# BMW_final.net
KiCad netlist of a schematic drawn in EAGLE
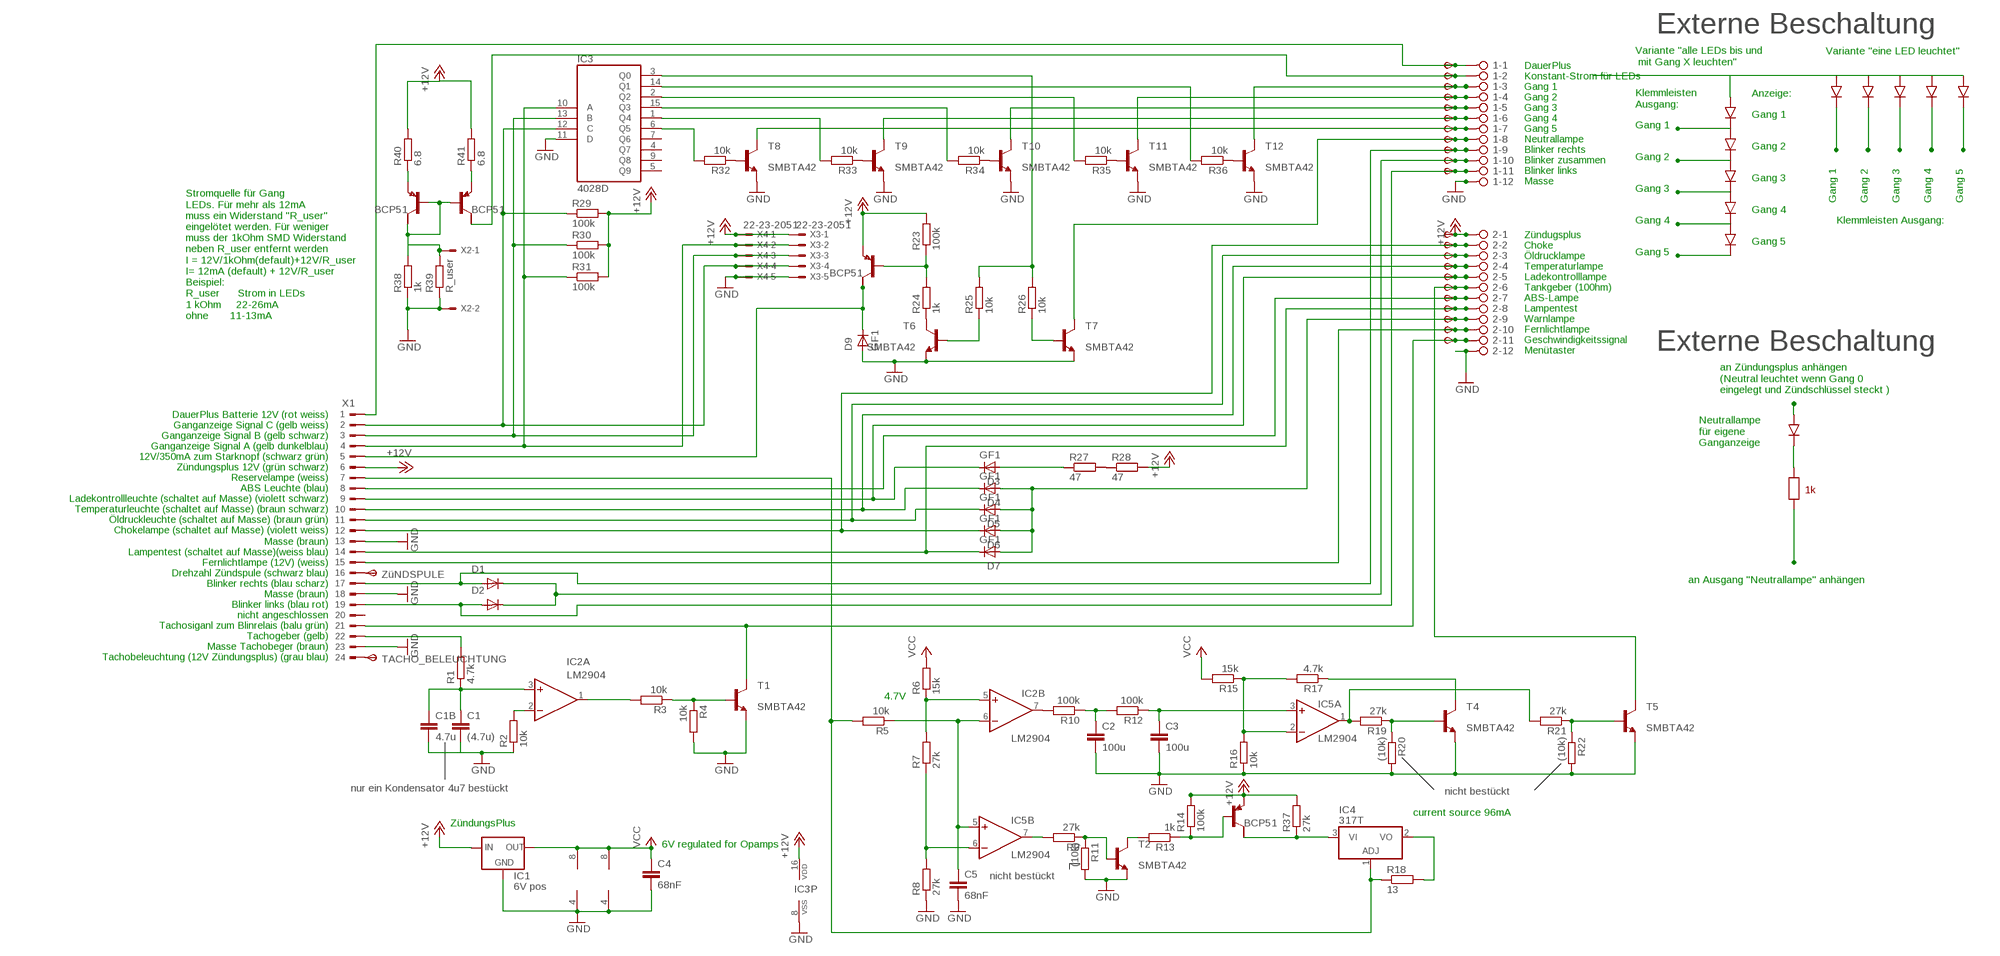
[diagram p0: schematic, sheet 1]

(export (version "E")
  (design (tool "Eeschema 10.0.6"))
  (components
    (comp (ref "1")
      (value "2081-1132")
      (footprint "eagle-import:12-PIN")
      (libsource (lib "eagle-import") (part "2081-1132"))
    )
    (comp (ref "2")
      (value "2081-1132")
      (footprint "eagle-import:12-PIN")
      (libsource (lib "eagle-import") (part "2081-1132"))
    )
    (comp (ref "C1")
      (value "(4.7u)")
      (footprint "eagle-import:C1206")
      (libsource (lib "eagle-import") (part "C-EUC1206"))
    )
    (comp (ref "C1B")
      (value "4.7u")
      (footprint "eagle-import:C0805K")
      (libsource (lib "eagle-import") (part "C-EUC0805K"))
    )
    (comp (ref "C2")
      (value "100u")
      (footprint "eagle-import:C1206K")
      (libsource (lib "eagle-import") (part "C-EUC1206K"))
    )
    (comp (ref "C3")
      (value "100u")
      (footprint "eagle-import:C1206K")
      (libsource (lib "eagle-import") (part "C-EUC1206K"))
    )
    (comp (ref "C4")
      (value "68nF")
      (footprint "eagle-import:C1206K")
      (libsource (lib "eagle-import") (part "C-EUC1206K"))
    )
    (comp (ref "C5")
      (value "68nF")
      (footprint "eagle-import:C1206K")
      (libsource (lib "eagle-import") (part "C-EUC1206K"))
    )
    (comp (ref "D1")
      (value "GF1")
      (footprint "eagle-import:SMA-DO214AC")
      (libsource (lib "eagle-import") (part "GF1"))
    )
    (comp (ref "D2")
      (value "GF1")
      (footprint "eagle-import:SMA-DO214AC")
      (libsource (lib "eagle-import") (part "GF1"))
    )
    (comp (ref "D3")
      (value "GF1")
      (footprint "eagle-import:SMA-DO214AC")
      (libsource (lib "eagle-import") (part "GF1"))
    )
    (comp (ref "D4")
      (value "GF1")
      (footprint "eagle-import:SMA-DO214AC")
      (libsource (lib "eagle-import") (part "GF1"))
    )
    (comp (ref "D5")
      (value "GF1")
      (footprint "eagle-import:SMA-DO214AC")
      (libsource (lib "eagle-import") (part "GF1"))
    )
    (comp (ref "D6")
      (value "GF1")
      (footprint "eagle-import:SMA-DO214AC")
      (libsource (lib "eagle-import") (part "GF1"))
    )
    (comp (ref "D7")
      (value "GF1")
      (footprint "eagle-import:SMA-DO214AC")
      (libsource (lib "eagle-import") (part "GF1"))
    )
    (comp (ref "D9")
      (value "GF1")
      (footprint "eagle-import:SMA-DO214AC")
      (libsource (lib "eagle-import") (part "GF1"))
    )
    (comp (ref "IC1")
      (value "6V pos")
      (footprint "eagle-import:78LXX")
      (libsource (lib "eagle-import") (part "78LXX"))
    )
    (comp (ref "IC2")
      (value "LM2904")
      (footprint "eagle-import:SO08")
      (fields (field (name "IC") "LM2904"))
      (libsource (lib "eagle-import") (part "LM358D"))
    )
    (comp (ref "IC3")
      (value "4028D")
      (footprint "eagle-import:SO16")
      (libsource (lib "eagle-import") (part "4028D"))
    )
    (comp (ref "IC4")
      (value "317T")
      (footprint "eagle-import:TO220H")
      (libsource (lib "eagle-import") (part "317T"))
    )
    (comp (ref "IC5")
      (value "LM2904")
      (footprint "eagle-import:SO08")
      (libsource (lib "eagle-import") (part "linear_BMW_LM358D"))
    )
    (comp (ref "R1")
      (value "4.7k")
      (footprint "eagle-import:R0805")
      (libsource (lib "eagle-import") (part "R-EU_R0805"))
    )
    (comp (ref "R2")
      (value "10k")
      (footprint "eagle-import:R0805")
      (libsource (lib "eagle-import") (part "R-EU_R0805"))
    )
    (comp (ref "R3")
      (value "10k")
      (footprint "eagle-import:R0805")
      (libsource (lib "eagle-import") (part "R-EU_R0805"))
    )
    (comp (ref "R4")
      (value "10k")
      (footprint "eagle-import:R0805")
      (libsource (lib "eagle-import") (part "R-EU_R0805"))
    )
    (comp (ref "R5")
      (value "10k")
      (footprint "eagle-import:R0805")
      (libsource (lib "eagle-import") (part "R-EU_R0805"))
    )
    (comp (ref "R6")
      (value "15k")
      (footprint "eagle-import:R0805")
      (libsource (lib "eagle-import") (part "R-EU_R0805"))
    )
    (comp (ref "R7")
      (value "27k")
      (footprint "eagle-import:R0805")
      (libsource (lib "eagle-import") (part "R-EU_R0805"))
    )
    (comp (ref "R8")
      (value "27k")
      (footprint "eagle-import:R0805")
      (libsource (lib "eagle-import") (part "R-EU_R0805"))
    )
    (comp (ref "R9")
      (value "27k")
      (footprint "eagle-import:R0805")
      (libsource (lib "eagle-import") (part "R-EU_R0805"))
    )
    (comp (ref "R10")
      (value "100k")
      (footprint "eagle-import:R0805")
      (libsource (lib "eagle-import") (part "R-EU_R0805"))
    )
    (comp (ref "R11")
      (value "(10k)")
      (footprint "eagle-import:R0805")
      (libsource (lib "eagle-import") (part "R-EU_R0805"))
    )
    (comp (ref "R12")
      (value "100k")
      (footprint "eagle-import:R0805")
      (libsource (lib "eagle-import") (part "R-EU_R0805"))
    )
    (comp (ref "R13")
      (value "1k")
      (footprint "eagle-import:R0805")
      (libsource (lib "eagle-import") (part "R-EU_R0805"))
    )
    (comp (ref "R14")
      (value "100k")
      (footprint "eagle-import:R0805")
      (libsource (lib "eagle-import") (part "R-EU_R0805"))
    )
    (comp (ref "R15")
      (value "15k")
      (footprint "eagle-import:R0805")
      (libsource (lib "eagle-import") (part "R-EU_R0805"))
    )
    (comp (ref "R16")
      (value "10k")
      (footprint "eagle-import:R0805")
      (libsource (lib "eagle-import") (part "R-EU_R0805"))
    )
    (comp (ref "R17")
      (value "4.7k")
      (footprint "eagle-import:R0805")
      (libsource (lib "eagle-import") (part "R-EU_R0805"))
    )
    (comp (ref "R18")
      (value "13")
      (footprint "eagle-import:0207_10")
      (libsource (lib "eagle-import") (part "R-EU_0207/10"))
    )
    (comp (ref "R19")
      (value "27k")
      (footprint "eagle-import:R0805")
      (libsource (lib "eagle-import") (part "R-EU_R0805"))
    )
    (comp (ref "R20")
      (value "(10k)")
      (footprint "eagle-import:R0805")
      (libsource (lib "eagle-import") (part "R-EU_R0805"))
    )
    (comp (ref "R21")
      (value "27k")
      (footprint "eagle-import:R0805")
      (libsource (lib "eagle-import") (part "R-EU_R0805"))
    )
    (comp (ref "R22")
      (value "(10k)")
      (footprint "eagle-import:R0805")
      (libsource (lib "eagle-import") (part "R-EU_R0805"))
    )
    (comp (ref "R23")
      (value "100k")
      (footprint "eagle-import:R0805")
      (libsource (lib "eagle-import") (part "R-EU_R0805"))
    )
    (comp (ref "R24")
      (value "1k")
      (footprint "eagle-import:R0805")
      (libsource (lib "eagle-import") (part "R-EU_R0805"))
    )
    (comp (ref "R25")
      (value "10k")
      (footprint "eagle-import:R0805")
      (libsource (lib "eagle-import") (part "R-EU_R0805"))
    )
    (comp (ref "R26")
      (value "10k")
      (footprint "eagle-import:R0805")
      (libsource (lib "eagle-import") (part "R-EU_R0805"))
    )
    (comp (ref "R27")
      (value "47")
      (footprint "eagle-import:V235_17")
      (libsource (lib "eagle-import") (part "R-EU_V235/17"))
    )
    (comp (ref "R28")
      (value "47")
      (footprint "eagle-import:V235_17")
      (libsource (lib "eagle-import") (part "R-EU_V235/17"))
    )
    (comp (ref "R29")
      (value "100k")
      (footprint "eagle-import:R0805")
      (libsource (lib "eagle-import") (part "R-EU_R0805"))
    )
    (comp (ref "R30")
      (value "100k")
      (footprint "eagle-import:R0805")
      (libsource (lib "eagle-import") (part "R-EU_R0805"))
    )
    (comp (ref "R31")
      (value "100k")
      (footprint "eagle-import:R0805")
      (libsource (lib "eagle-import") (part "R-EU_R0805"))
    )
    (comp (ref "R32")
      (value "10k")
      (footprint "eagle-import:R0805")
      (libsource (lib "eagle-import") (part "R-EU_R0805"))
    )
    (comp (ref "R33")
      (value "10k")
      (footprint "eagle-import:R0805")
      (libsource (lib "eagle-import") (part "R-EU_R0805"))
    )
    (comp (ref "R34")
      (value "10k")
      (footprint "eagle-import:R0805")
      (libsource (lib "eagle-import") (part "R-EU_R0805"))
    )
    (comp (ref "R35")
      (value "10k")
      (footprint "eagle-import:R0805")
      (libsource (lib "eagle-import") (part "R-EU_R0805"))
    )
    (comp (ref "R36")
      (value "10k")
      (footprint "eagle-import:R0805")
      (libsource (lib "eagle-import") (part "R-EU_R0805"))
    )
    (comp (ref "R37")
      (value "27k")
      (footprint "eagle-import:R0805")
      (libsource (lib "eagle-import") (part "R-EU_R0805"))
    )
    (comp (ref "R38")
      (value "1k")
      (footprint "eagle-import:R0805")
      (libsource (lib "eagle-import") (part "R-EU_R0805"))
    )
    (comp (ref "R39")
      (value "R_user")
      (footprint "eagle-import:R0805")
      (libsource (lib "eagle-import") (part "R-EU_R0805"))
    )
    (comp (ref "R40")
      (value "6.8")
      (footprint "eagle-import:R0805")
      (libsource (lib "eagle-import") (part "R-EU_R0805"))
    )
    (comp (ref "R41")
      (value "6.8")
      (footprint "eagle-import:R0805")
      (libsource (lib "eagle-import") (part "R-EU_R0805"))
    )
    (comp (ref "T")
      (value "BCP53T1")
      (footprint "eagle-import:SOT223")
      (fields (field (name "T") "BCP51"))
      (libsource (lib "eagle-import") (part "BCP53T1"))
    )
    (comp (ref "T1")
      (value "MMBTA42LT1-NPN-SOT23-BEC")
      (footprint "eagle-import:SOT23-BEC")
      (fields (field (name "T") "SMBTA42"))
      (libsource (lib "eagle-import") (part "-NPN-SOT23-BECMMBTA42LT1"))
    )
    (comp (ref "T2")
      (value "MMBTA42LT1-NPN-SOT23-BEC")
      (footprint "eagle-import:SOT23-BEC")
      (fields (field (name "T") "SMBTA42"))
      (libsource (lib "eagle-import") (part "-NPN-SOT23-BECMMBTA42LT1"))
    )
    (comp (ref "T3")
      (value "BCP53T1")
      (footprint "eagle-import:SOT223")
      (fields (field (name "T") "BCP51"))
      (libsource (lib "eagle-import") (part "BCP53T1"))
    )
    (comp (ref "T4")
      (value "MMBTA42LT1-NPN-SOT23-BEC")
      (footprint "eagle-import:SOT23-BEC")
      (fields (field (name "T") "SMBTA42"))
      (libsource (lib "eagle-import") (part "-NPN-SOT23-BECMMBTA42LT1"))
    )
    (comp (ref "T5")
      (value "MMBTA42LT1-NPN-SOT23-BEC")
      (footprint "eagle-import:SOT23-BEC")
      (fields (field (name "T") "SMBTA42"))
      (libsource (lib "eagle-import") (part "-NPN-SOT23-BECMMBTA42LT1"))
    )
    (comp (ref "T6")
      (value "MMBTA42LT1-NPN-SOT23-BEC")
      (footprint "eagle-import:SOT23-BEC")
      (fields (field (name "T") "SMBTA42"))
      (libsource (lib "eagle-import") (part "-NPN-SOT23-BECMMBTA42LT1"))
    )
    (comp (ref "T7")
      (value "MMBTA42LT1-NPN-SOT23-BEC")
      (footprint "eagle-import:SOT23-BEC")
      (fields (field (name "T") "SMBTA42"))
      (libsource (lib "eagle-import") (part "-NPN-SOT23-BECMMBTA42LT1"))
    )
    (comp (ref "T8")
      (value "MMBTA42LT1-NPN-SOT23-BEC")
      (footprint "eagle-import:SOT23-BEC")
      (fields (field (name "T") "SMBTA42"))
      (libsource (lib "eagle-import") (part "-NPN-SOT23-BECMMBTA42LT1"))
    )
    (comp (ref "T9")
      (value "MMBTA42LT1-NPN-SOT23-BEC")
      (footprint "eagle-import:SOT23-BEC")
      (fields (field (name "T") "SMBTA42"))
      (libsource (lib "eagle-import") (part "-NPN-SOT23-BECMMBTA42LT1"))
    )
    (comp (ref "T10")
      (value "MMBTA42LT1-NPN-SOT23-BEC")
      (footprint "eagle-import:SOT23-BEC")
      (fields (field (name "T") "SMBTA42"))
      (libsource (lib "eagle-import") (part "-NPN-SOT23-BECMMBTA42LT1"))
    )
    (comp (ref "T11")
      (value "MMBTA42LT1-NPN-SOT23-BEC")
      (footprint "eagle-import:SOT23-BEC")
      (fields (field (name "T") "SMBTA42"))
      (libsource (lib "eagle-import") (part "-NPN-SOT23-BECMMBTA42LT1"))
    )
    (comp (ref "T12")
      (value "MMBTA42LT1-NPN-SOT23-BEC")
      (footprint "eagle-import:SOT23-BEC")
      (fields (field (name "T") "SMBTA42"))
      (libsource (lib "eagle-import") (part "-NPN-SOT23-BECMMBTA42LT1"))
    )
    (comp (ref "T13")
      (value "BCP53T1")
      (footprint "eagle-import:SOT223")
      (fields (field (name "T") "BCP51"))
      (libsource (lib "eagle-import") (part "BCP53T1"))
    )
    (comp (ref "T14")
      (value "BCP53T1")
      (footprint "eagle-import:SOT223")
      (fields (field (name "T") "BCP51"))
      (libsource (lib "eagle-import") (part "BCP53T1"))
    )
    (comp (ref "TACHO_BELEUCHTUNG")
      (value "TPSP1_1MM")
      (footprint "eagle-import:P1_1.0MM")
      (libsource (lib "eagle-import") (part "TPSP1_1MM"))
    )
    (comp (ref "TP1")
      (value "TPSB1,27")
      (footprint "eagle-import:B1,27")
      (libsource (lib "eagle-import") (part "TPSB1,27"))
    )
    (comp (ref "TP2")
      (value "TPSB1,27")
      (footprint "eagle-import:B1,27")
      (libsource (lib "eagle-import") (part "TPSB1,27"))
    )
    (comp (ref "TP3")
      (value "TPSB1,27")
      (footprint "eagle-import:B1,27")
      (libsource (lib "eagle-import") (part "TPSB1,27"))
    )
    (comp (ref "TP4")
      (value "TPSB1,27")
      (footprint "eagle-import:B1,27")
      (libsource (lib "eagle-import") (part "TPSB1,27"))
    )
    (comp (ref "TP5")
      (value "TPSB1,27")
      (footprint "eagle-import:B1,27")
      (libsource (lib "eagle-import") (part "TPSB1,27"))
    )
    (comp (ref "TP6")
      (value "TPSB1,27")
      (footprint "eagle-import:B1,27")
      (libsource (lib "eagle-import") (part "TPSB1,27"))
    )
    (comp (ref "TP7")
      (value "TPSB1,27")
      (footprint "eagle-import:B1,27")
      (libsource (lib "eagle-import") (part "TPSB1,27"))
    )
    (comp (ref "TP8")
      (value "TPSB1,27")
      (footprint "eagle-import:B1,27")
      (libsource (lib "eagle-import") (part "TPSB1,27"))
    )
    (comp (ref "TP9")
      (value "TPSB1,27")
      (footprint "eagle-import:B1,27")
      (libsource (lib "eagle-import") (part "TPSB1,27"))
    )
    (comp (ref "TP10")
      (value "TPSB1,27")
      (footprint "eagle-import:B1,27")
      (libsource (lib "eagle-import") (part "TPSB1,27"))
    )
    (comp (ref "TP11")
      (value "TPSB1,27")
      (footprint "eagle-import:B1,27")
      (libsource (lib "eagle-import") (part "TPSB1,27"))
    )
    (comp (ref "TP12")
      (value "TPSB1,27")
      (footprint "eagle-import:B1,27")
      (libsource (lib "eagle-import") (part "TPSB1,27"))
    )
    (comp (ref "TP16")
      (value "TPSB1,27")
      (footprint "eagle-import:B1,27")
      (libsource (lib "eagle-import") (part "TPSB1,27"))
    )
    (comp (ref "TP17")
      (value "TPSB1,27")
      (footprint "eagle-import:B1,27")
      (libsource (lib "eagle-import") (part "TPSB1,27"))
    )
    (comp (ref "TP18")
      (value "TPSB1,27")
      (footprint "eagle-import:B1,27")
      (libsource (lib "eagle-import") (part "TPSB1,27"))
    )
    (comp (ref "TP19")
      (value "TPSB1,27")
      (footprint "eagle-import:B1,27")
      (libsource (lib "eagle-import") (part "TPSB1,27"))
    )
    (comp (ref "TP21")
      (value "TPSB1,27")
      (footprint "eagle-import:B1,27")
      (libsource (lib "eagle-import") (part "TPSB1,27"))
    )
    (comp (ref "TP22")
      (value "TPSB1,27")
      (footprint "eagle-import:B1,27")
      (libsource (lib "eagle-import") (part "TPSB1,27"))
    )
    (comp (ref "TP23")
      (value "TPSB1,27")
      (footprint "eagle-import:B1,27")
      (libsource (lib "eagle-import") (part "TPSB1,27"))
    )
    (comp (ref "TP24")
      (value "TPSB1,27")
      (footprint "eagle-import:B1,27")
      (libsource (lib "eagle-import") (part "TPSB1,27"))
    )
    (comp (ref "TP25")
      (value "TPSB1,27")
      (footprint "eagle-import:B1,27")
      (libsource (lib "eagle-import") (part "TPSB1,27"))
    )
    (comp (ref "TP26")
      (value "TPSB1,27")
      (footprint "eagle-import:B1,27")
      (libsource (lib "eagle-import") (part "TPSB1,27"))
    )
    (comp (ref "X1")
      (value "CON_BMW")
      (footprint "eagle-import:24-PIN")
      (libsource (lib "eagle-import") (part "CON_BMW"))
    )
    (comp (ref "X2")
      (value "22-23-2021")
      (footprint "eagle-import:22-23-2021")
      (fields (field (name "MF") "MOLEX"))
      (libsource (lib "eagle-import") (part "22-23-2021"))
    )
    (comp (ref "X3")
      (value "22-23-2051")
      (footprint "eagle-import:22-23-2051")
      (fields (field (name "MF") "MOLEX"))
      (libsource (lib "eagle-import") (part "22-23-2051"))
    )
    (comp (ref "X4")
      (value "22-23-2051")
      (footprint "eagle-import:22-23-2051")
      (fields (field (name "MF") "MOLEX"))
      (libsource (lib "eagle-import") (part "22-23-2051"))
    )
    (comp (ref "ZüNDSPULE")
      (value "TPSP1_1MM")
      (footprint "eagle-import:P1_1.0MM")
      (libsource (lib "eagle-import") (part "TPSP1_1MM"))
    )
  )
  (nets
    (net (code "1") (name "+12V") (class "Default")
      (node (ref "2") (pin "1") (pinfunction "KL_1") (pintype "passive"))
      (node (ref "IC1") (pin "IN") (pinfunction "IN_IN") (pintype "input"))
      (node (ref "IC3") (pin "16") (pinfunction "VDD_16") (pintype "power_in"))
      (node (ref "R14") (pin "2") (pinfunction "2_2") (pintype "passive"))
      (node (ref "R23") (pin "2") (pinfunction "2_2") (pintype "passive"))
      (node (ref "R28") (pin "2") (pinfunction "2_2") (pintype "passive"))
      (node (ref "R29") (pin "2") (pinfunction "2_2") (pintype "passive"))
      (node (ref "R30") (pin "2") (pinfunction "2_2") (pintype "passive"))
      (node (ref "R31") (pin "2") (pinfunction "2_2") (pintype "passive"))
      (node (ref "R37") (pin "2") (pinfunction "2_2") (pintype "passive"))
      (node (ref "R40") (pin "2") (pinfunction "2_2") (pintype "passive"))
      (node (ref "R41") (pin "2") (pinfunction "2_2") (pintype "passive"))
      (node (ref "T") (pin "3") (pinfunction "E_3") (pintype "passive"))
      (node (ref "T3") (pin "3") (pinfunction "E_3") (pintype "passive"))
      (node (ref "TP12") (pin "TP") (pinfunction "PP_TP") (pintype "input"))
      (node (ref "X1") (pin "6") (pinfunction "6_6") (pintype "passive"))
      (node (ref "X3") (pin "1") (pinfunction "S_1") (pintype "passive"))
      (node (ref "X4") (pin "1") (pinfunction "S_1") (pintype "passive"))
    )
    (net (code "2") (name "GND") (class "Default")
      (node (ref "1") (pin "12") (pinfunction "KL_12") (pintype "passive"))
      (node (ref "2") (pin "12") (pinfunction "KL_12") (pintype "passive"))
      (node (ref "C1") (pin "2") (pinfunction "2_2") (pintype "passive"))
      (node (ref "C1B") (pin "2") (pinfunction "2_2") (pintype "passive"))
      (node (ref "C2") (pin "2") (pinfunction "2_2") (pintype "passive"))
      (node (ref "C3") (pin "2") (pinfunction "2_2") (pintype "passive"))
      (node (ref "C4") (pin "2") (pinfunction "2_2") (pintype "passive"))
      (node (ref "C5") (pin "2") (pinfunction "2_2") (pintype "passive"))
      (node (ref "D9") (pin "A") (pinfunction "A_A") (pintype "passive"))
      (node (ref "IC1") (pin "GND") (pinfunction "GND_GND") (pintype "input"))
      (node (ref "IC2") (pin "4") (pinfunction "V-_4") (pintype "power_in"))
      (node (ref "IC3") (pin "11") (pinfunction "D_11") (pintype "input"))
      (node (ref "IC3") (pin "8") (pinfunction "VSS_8") (pintype "power_in"))
      (node (ref "IC5") (pin "4") (pinfunction "V-_4") (pintype "power_in"))
      (node (ref "R11") (pin "2") (pinfunction "2_2") (pintype "passive"))
      (node (ref "R16") (pin "1") (pinfunction "1_1") (pintype "passive"))
      (node (ref "R2") (pin "1") (pinfunction "1_1") (pintype "passive"))
      (node (ref "R20") (pin "2") (pinfunction "2_2") (pintype "passive"))
      (node (ref "R22") (pin "2") (pinfunction "2_2") (pintype "passive"))
      (node (ref "R38") (pin "1") (pinfunction "1_1") (pintype "passive"))
      (node (ref "R39") (pin "1") (pinfunction "1_1") (pintype "passive"))
      (node (ref "R4") (pin "2") (pinfunction "2_2") (pintype "passive"))
      (node (ref "R8") (pin "1") (pinfunction "1_1") (pintype "passive"))
      (node (ref "T1") (pin "E") (pinfunction "E_E") (pintype "passive"))
      (node (ref "T10") (pin "E") (pinfunction "E_E") (pintype "passive"))
      (node (ref "T11") (pin "E") (pinfunction "E_E") (pintype "passive"))
      (node (ref "T12") (pin "E") (pinfunction "E_E") (pintype "passive"))
      (node (ref "T2") (pin "E") (pinfunction "E_E") (pintype "passive"))
      (node (ref "T4") (pin "E") (pinfunction "E_E") (pintype "passive"))
      (node (ref "T5") (pin "E") (pinfunction "E_E") (pintype "passive"))
      (node (ref "T6") (pin "E") (pinfunction "E_E") (pintype "passive"))
      (node (ref "T7") (pin "E") (pinfunction "E_E") (pintype "passive"))
      (node (ref "T8") (pin "E") (pinfunction "E_E") (pintype "passive"))
      (node (ref "T9") (pin "E") (pinfunction "E_E") (pintype "passive"))
      (node (ref "X1") (pin "13") (pinfunction "13_13") (pintype "passive"))
      (node (ref "X1") (pin "18") (pinfunction "18_18") (pintype "passive"))
      (node (ref "X1") (pin "23") (pinfunction "23_23") (pintype "passive"))
      (node (ref "X2") (pin "2") (pinfunction "S_2") (pintype "passive"))
      (node (ref "X3") (pin "5") (pinfunction "S_5") (pintype "passive"))
      (node (ref "X4") (pin "5") (pinfunction "S_5") (pintype "passive"))
    )
    (net (code "3") (name "Net-(1A-KL)") (class "Default")
      (node (ref "1") (pin "1") (pinfunction "KL_1") (pintype "passive"))
      (node (ref "TP1") (pin "TP") (pinfunction "PP_TP") (pintype "input"))
      (node (ref "X1") (pin "1") (pinfunction "1_1") (pintype "passive"))
    )
    (net (code "4") (name "Net-(1B-KL)") (class "Default")
      (node (ref "1") (pin "10") (pinfunction "KL_10") (pintype "passive"))
      (node (ref "D1") (pin "K") (pinfunction "C_K") (pintype "passive"))
      (node (ref "D2") (pin "K") (pinfunction "C_K") (pintype "passive"))
      (node (ref "TP10") (pin "TP") (pinfunction "PP_TP") (pintype "input"))
    )
    (net (code "5") (name "Net-(1C-KL)") (class "Default")
      (node (ref "1") (pin "11") (pinfunction "KL_11") (pintype "passive"))
      (node (ref "D2") (pin "A") (pinfunction "A_A") (pintype "passive"))
      (node (ref "TP11") (pin "TP") (pinfunction "PP_TP") (pintype "input"))
      (node (ref "X1") (pin "19") (pinfunction "19_19") (pintype "passive"))
    )
    (net (code "6") (name "Net-(1E-KL)") (class "Default")
      (node (ref "1") (pin "2") (pinfunction "KL_2") (pintype "passive"))
      (node (ref "T14") (pin "2") (pinfunction "C_2") (pintype "passive"))
      (node (ref "TP2") (pin "TP") (pinfunction "PP_TP") (pintype "input"))
    )
    (net (code "7") (name "Net-(1F-KL)") (class "Default")
      (node (ref "1") (pin "3") (pinfunction "KL_3") (pintype "passive"))
      (node (ref "T12") (pin "C") (pinfunction "C_C") (pintype "passive"))
      (node (ref "TP3") (pin "TP") (pinfunction "PP_TP") (pintype "input"))
    )
    (net (code "8") (name "Net-(1G-KL)") (class "Default")
      (node (ref "1") (pin "4") (pinfunction "KL_4") (pintype "passive"))
      (node (ref "T11") (pin "C") (pinfunction "C_C") (pintype "passive"))
      (node (ref "TP4") (pin "TP") (pinfunction "PP_TP") (pintype "input"))
    )
    (net (code "9") (name "Net-(1H-KL)") (class "Default")
      (node (ref "1") (pin "5") (pinfunction "KL_5") (pintype "passive"))
      (node (ref "T10") (pin "C") (pinfunction "C_C") (pintype "passive"))
      (node (ref "TP5") (pin "TP") (pinfunction "PP_TP") (pintype "input"))
    )
    (net (code "10") (name "Net-(1I-KL)") (class "Default")
      (node (ref "1") (pin "6") (pinfunction "KL_6") (pintype "passive"))
      (node (ref "T9") (pin "C") (pinfunction "C_C") (pintype "passive"))
      (node (ref "TP6") (pin "TP") (pinfunction "PP_TP") (pintype "input"))
    )
    (net (code "11") (name "Net-(1J-KL)") (class "Default")
      (node (ref "1") (pin "7") (pinfunction "KL_7") (pintype "passive"))
      (node (ref "T8") (pin "C") (pinfunction "C_C") (pintype "passive"))
      (node (ref "TP7") (pin "TP") (pinfunction "PP_TP") (pintype "input"))
    )
    (net (code "12") (name "Net-(1K-KL)") (class "Default")
      (node (ref "1") (pin "8") (pinfunction "KL_8") (pintype "passive"))
      (node (ref "T7") (pin "C") (pinfunction "C_C") (pintype "passive"))
      (node (ref "TP8") (pin "TP") (pinfunction "PP_TP") (pintype "input"))
    )
    (net (code "13") (name "Net-(1L-KL)") (class "Default")
      (node (ref "1") (pin "9") (pinfunction "KL_9") (pintype "passive"))
      (node (ref "D1") (pin "A") (pinfunction "A_A") (pintype "passive"))
      (node (ref "TP9") (pin "TP") (pinfunction "PP_TP") (pintype "input"))
      (node (ref "X1") (pin "17") (pinfunction "17_17") (pintype "passive"))
    )
    (net (code "14") (name "Net-(2B-KL)") (class "Default")
      (node (ref "2") (pin "10") (pinfunction "KL_10") (pintype "passive"))
      (node (ref "TP25") (pin "TP") (pinfunction "PP_TP") (pintype "input"))
      (node (ref "X1") (pin "15") (pinfunction "15_15") (pintype "passive"))
    )
    (net (code "15") (name "Net-(2C-KL)") (class "Default")
      (node (ref "2") (pin "11") (pinfunction "KL_11") (pintype "passive"))
      (node (ref "T1") (pin "C") (pinfunction "C_C") (pintype "passive"))
      (node (ref "TP26") (pin "TP") (pinfunction "PP_TP") (pintype "input"))
      (node (ref "X1") (pin "21") (pinfunction "21_21") (pintype "passive"))
    )
    (net (code "16") (name "Net-(2E-KL)") (class "Default")
      (node (ref "2") (pin "2") (pinfunction "KL_2") (pintype "passive"))
      (node (ref "D6") (pin "K") (pinfunction "C_K") (pintype "passive"))
      (node (ref "TP16") (pin "TP") (pinfunction "PP_TP") (pintype "input"))
      (node (ref "X1") (pin "12") (pinfunction "12_12") (pintype "passive"))
    )
    (net (code "17") (name "Net-(2F-KL)") (class "Default")
      (node (ref "2") (pin "3") (pinfunction "KL_3") (pintype "passive"))
      (node (ref "D5") (pin "K") (pinfunction "C_K") (pintype "passive"))
      (node (ref "TP17") (pin "TP") (pinfunction "PP_TP") (pintype "input"))
      (node (ref "X1") (pin "11") (pinfunction "11_11") (pintype "passive"))
    )
    (net (code "18") (name "Net-(2G-KL)") (class "Default")
      (node (ref "2") (pin "4") (pinfunction "KL_4") (pintype "passive"))
      (node (ref "D4") (pin "K") (pinfunction "C_K") (pintype "passive"))
      (node (ref "TP18") (pin "TP") (pinfunction "PP_TP") (pintype "input"))
      (node (ref "X1") (pin "10") (pinfunction "10_10") (pintype "passive"))
    )
    (net (code "19") (name "Net-(2H-KL)") (class "Default")
      (node (ref "2") (pin "5") (pinfunction "KL_5") (pintype "passive"))
      (node (ref "D3") (pin "K") (pinfunction "C_K") (pintype "passive"))
      (node (ref "TP19") (pin "TP") (pinfunction "PP_TP") (pintype "input"))
      (node (ref "X1") (pin "9") (pinfunction "9_9") (pintype "passive"))
    )
    (net (code "20") (name "Net-(2I-KL)") (class "Default")
      (node (ref "2") (pin "6") (pinfunction "KL_6") (pintype "passive"))
      (node (ref "T5") (pin "C") (pinfunction "C_C") (pintype "passive"))
      (node (ref "TP21") (pin "TP") (pinfunction "PP_TP") (pintype "input"))
    )
    (net (code "21") (name "Net-(2J-KL)") (class "Default")
      (node (ref "2") (pin "7") (pinfunction "KL_7") (pintype "passive"))
      (node (ref "TP22") (pin "TP") (pinfunction "PP_TP") (pintype "input"))
      (node (ref "X1") (pin "8") (pinfunction "8_8") (pintype "passive"))
    )
    (net (code "22") (name "Net-(2K-KL)") (class "Default")
      (node (ref "2") (pin "8") (pinfunction "KL_8") (pintype "passive"))
      (node (ref "D7") (pin "K") (pinfunction "C_K") (pintype "passive"))
      (node (ref "TP23") (pin "TP") (pinfunction "PP_TP") (pintype "input"))
      (node (ref "X1") (pin "14") (pinfunction "14_14") (pintype "passive"))
    )
    (net (code "23") (name "Net-(2L-KL)") (class "Default")
      (node (ref "2") (pin "9") (pinfunction "KL_9") (pintype "passive"))
      (node (ref "D4") (pin "A") (pinfunction "A_A") (pintype "passive"))
      (node (ref "D5") (pin "A") (pinfunction "A_A") (pintype "passive"))
      (node (ref "D6") (pin "A") (pinfunction "A_A") (pintype "passive"))
      (node (ref "D7") (pin "A") (pinfunction "A_A") (pintype "passive"))
      (node (ref "TP24") (pin "TP") (pinfunction "PP_TP") (pintype "input"))
    )
    (net (code "24") (name "Net-(C2-Pad1)") (class "Default")
      (node (ref "C2") (pin "1") (pinfunction "1_1") (pintype "passive"))
      (node (ref "R10") (pin "1") (pinfunction "1_1") (pintype "passive"))
      (node (ref "R12") (pin "2") (pinfunction "2_2") (pintype "passive"))
    )
    (net (code "25") (name "Net-(D3-PadA)") (class "Default")
      (node (ref "D3") (pin "A") (pinfunction "A_A") (pintype "passive"))
      (node (ref "R27") (pin "1") (pinfunction "1_1") (pintype "passive"))
    )
    (net (code "26") (name "Net-(D9-C)") (class "Default")
      (node (ref "D9") (pin "K") (pinfunction "C_K") (pintype "passive"))
      (node (ref "T") (pin "2") (pinfunction "C_2") (pintype "passive"))
      (node (ref "X1") (pin "5") (pinfunction "5_5") (pintype "passive"))
    )
    (net (code "27") (name "Net-(IC2A-+IN)") (class "Default")
      (node (ref "C1") (pin "1") (pinfunction "1_1") (pintype "passive"))
      (node (ref "C1B") (pin "1") (pinfunction "1_1") (pintype "passive"))
      (node (ref "IC2") (pin "3") (pinfunction "+IN_3") (pintype "input"))
      (node (ref "R1") (pin "1") (pinfunction "1_1") (pintype "passive"))
    )
    (net (code "28") (name "Net-(IC2A--IN)") (class "Default")
      (node (ref "IC2") (pin "2") (pinfunction "-IN_2") (pintype "input"))
      (node (ref "R2") (pin "2") (pinfunction "2_2") (pintype "passive"))
    )
    (net (code "29") (name "Net-(IC2A-OUT)") (class "Default")
      (node (ref "IC2") (pin "1") (pinfunction "OUT_1") (pintype "output"))
      (node (ref "R3") (pin "2") (pinfunction "2_2") (pintype "passive"))
    )
    (net (code "30") (name "Net-(IC2B-+IN)") (class "Default")
      (node (ref "IC2") (pin "5") (pinfunction "+IN_5") (pintype "input"))
      (node (ref "R6") (pin "1") (pinfunction "1_1") (pintype "passive"))
      (node (ref "R7") (pin "2") (pinfunction "2_2") (pintype "passive"))
    )
    (net (code "31") (name "Net-(IC2B--IN)") (class "Default")
      (node (ref "C5") (pin "1") (pinfunction "1_1") (pintype "passive"))
      (node (ref "IC2") (pin "6") (pinfunction "-IN_6") (pintype "input"))
      (node (ref "IC5") (pin "5") (pinfunction "+IN_5") (pintype "input"))
      (node (ref "R5") (pin "1") (pinfunction "1_1") (pintype "passive"))
    )
    (net (code "32") (name "Net-(IC2B-OUT)") (class "Default")
      (node (ref "IC2") (pin "7") (pinfunction "OUT_7") (pintype "output"))
      (node (ref "R10") (pin "2") (pinfunction "2_2") (pintype "passive"))
    )
    (net (code "33") (name "Net-(IC3A-A)") (class "Default")
      (node (ref "IC3") (pin "10") (pinfunction "A_10") (pintype "input"))
      (node (ref "R31") (pin "1") (pinfunction "1_1") (pintype "passive"))
      (node (ref "X1") (pin "4") (pinfunction "4_4") (pintype "passive"))
      (node (ref "X3") (pin "2") (pinfunction "S_2") (pintype "passive"))
      (node (ref "X4") (pin "2") (pinfunction "S_2") (pintype "passive"))
    )
    (net (code "34") (name "Net-(IC3A-B)") (class "Default")
      (node (ref "IC3") (pin "13") (pinfunction "B_13") (pintype "input"))
      (node (ref "R30") (pin "1") (pinfunction "1_1") (pintype "passive"))
      (node (ref "X1") (pin "3") (pinfunction "3_3") (pintype "passive"))
      (node (ref "X3") (pin "3") (pinfunction "S_3") (pintype "passive"))
      (node (ref "X4") (pin "3") (pinfunction "S_3") (pintype "passive"))
    )
    (net (code "35") (name "Net-(IC3A-C)") (class "Default")
      (node (ref "IC3") (pin "12") (pinfunction "C_12") (pintype "input"))
      (node (ref "R29") (pin "1") (pinfunction "1_1") (pintype "passive"))
      (node (ref "X1") (pin "2") (pinfunction "2_2") (pintype "passive"))
      (node (ref "X3") (pin "4") (pinfunction "S_4") (pintype "passive"))
      (node (ref "X4") (pin "4") (pinfunction "S_4") (pintype "passive"))
    )
    (net (code "36") (name "Net-(IC3A-Q0)") (class "Default")
      (node (ref "IC3") (pin "3") (pinfunction "Q0_3") (pintype "output"))
      (node (ref "R25") (pin "2") (pinfunction "2_2") (pintype "passive"))
      (node (ref "R26") (pin "2") (pinfunction "2_2") (pintype "passive"))
    )
    (net (code "37") (name "Net-(IC3A-Q1)") (class "Default")
      (node (ref "IC3") (pin "14") (pinfunction "Q1_14") (pintype "output"))
      (node (ref "R36") (pin "2") (pinfunction "2_2") (pintype "passive"))
    )
    (net (code "38") (name "Net-(IC3A-Q2)") (class "Default")
      (node (ref "IC3") (pin "2") (pinfunction "Q2_2") (pintype "output"))
      (node (ref "R35") (pin "2") (pinfunction "2_2") (pintype "passive"))
    )
    (net (code "39") (name "Net-(IC3A-Q3)") (class "Default")
      (node (ref "IC3") (pin "15") (pinfunction "Q3_15") (pintype "output"))
      (node (ref "R34") (pin "2") (pinfunction "2_2") (pintype "passive"))
    )
    (net (code "40") (name "Net-(IC3A-Q4)") (class "Default")
      (node (ref "IC3") (pin "1") (pinfunction "Q4_1") (pintype "output"))
      (node (ref "R33") (pin "2") (pinfunction "2_2") (pintype "passive"))
    )
    (net (code "41") (name "Net-(IC3A-Q5)") (class "Default")
      (node (ref "IC3") (pin "6") (pinfunction "Q5_6") (pintype "output"))
      (node (ref "R32") (pin "2") (pinfunction "2_2") (pintype "passive"))
    )
    (net (code "42") (name "Net-(IC4-ADJ)") (class "Default")
      (node (ref "IC4") (pin "1") (pinfunction "ADJ_1") (pintype "input"))
      (node (ref "R18") (pin "1") (pinfunction "1_1") (pintype "passive"))
      (node (ref "R5") (pin "2") (pinfunction "2_2") (pintype "passive"))
      (node (ref "X1") (pin "7") (pinfunction "7_7") (pintype "passive"))
    )
    (net (code "43") (name "Net-(IC4-VI)") (class "Default")
      (node (ref "IC4") (pin "3") (pinfunction "VI_3") (pintype "input"))
      (node (ref "R37") (pin "1") (pinfunction "1_1") (pintype "passive"))
      (node (ref "T3") (pin "2") (pinfunction "C_2") (pintype "passive"))
    )
    (net (code "44") (name "Net-(IC4-VO)") (class "Default")
      (node (ref "IC4") (pin "2") (pinfunction "VO_2") (pintype "passive"))
      (node (ref "R18") (pin "2") (pinfunction "2_2") (pintype "passive"))
    )
    (net (code "45") (name "Net-(IC5A-+IN)") (class "Default")
      (node (ref "C3") (pin "1") (pinfunction "1_1") (pintype "passive"))
      (node (ref "IC5") (pin "3") (pinfunction "+IN_3") (pintype "input"))
      (node (ref "R12") (pin "1") (pinfunction "1_1") (pintype "passive"))
    )
    (net (code "46") (name "Net-(IC5A--IN)") (class "Default")
      (node (ref "IC5") (pin "2") (pinfunction "-IN_2") (pintype "input"))
      (node (ref "R15") (pin "1") (pinfunction "1_1") (pintype "passive"))
      (node (ref "R16") (pin "2") (pinfunction "2_2") (pintype "passive"))
      (node (ref "R17") (pin "2") (pinfunction "2_2") (pintype "passive"))
    )
    (net (code "47") (name "Net-(IC5A-OUT)") (class "Default")
      (node (ref "IC5") (pin "1") (pinfunction "OUT_1") (pintype "output"))
      (node (ref "R19") (pin "2") (pinfunction "2_2") (pintype "passive"))
      (node (ref "R21") (pin "2") (pinfunction "2_2") (pintype "passive"))
    )
    (net (code "48") (name "Net-(IC5B--IN)") (class "Default")
      (node (ref "IC5") (pin "6") (pinfunction "-IN_6") (pintype "input"))
      (node (ref "R7") (pin "1") (pinfunction "1_1") (pintype "passive"))
      (node (ref "R8") (pin "2") (pinfunction "2_2") (pintype "passive"))
    )
    (net (code "49") (name "Net-(IC5B-OUT)") (class "Default")
      (node (ref "IC5") (pin "7") (pinfunction "OUT_7") (pintype "output"))
      (node (ref "R9") (pin "2") (pinfunction "2_2") (pintype "passive"))
    )
    (net (code "50") (name "Net-(R1-Pad2)") (class "Default")
      (node (ref "R1") (pin "2") (pinfunction "2_2") (pintype "passive"))
      (node (ref "X1") (pin "22") (pinfunction "22_22") (pintype "passive"))
    )
    (net (code "51") (name "Net-(R3-Pad1)") (class "Default")
      (node (ref "R3") (pin "1") (pinfunction "1_1") (pintype "passive"))
      (node (ref "R4") (pin "1") (pinfunction "1_1") (pintype "passive"))
      (node (ref "T1") (pin "B") (pinfunction "B_B") (pintype "passive"))
    )
    (net (code "52") (name "Net-(R11-Pad1)") (class "Default")
      (node (ref "R11") (pin "1") (pinfunction "1_1") (pintype "passive"))
      (node (ref "R9") (pin "1") (pinfunction "1_1") (pintype "passive"))
      (node (ref "T2") (pin "B") (pinfunction "B_B") (pintype "passive"))
    )
    (net (code "53") (name "Net-(R13-Pad2)") (class "Default")
      (node (ref "R13") (pin "2") (pinfunction "2_2") (pintype "passive"))
      (node (ref "T2") (pin "C") (pinfunction "C_C") (pintype "passive"))
    )
    (net (code "54") (name "Net-(R17-Pad1)") (class "Default")
      (node (ref "R17") (pin "1") (pinfunction "1_1") (pintype "passive"))
      (node (ref "T4") (pin "C") (pinfunction "C_C") (pintype "passive"))
    )
    (net (code "55") (name "Net-(R19-Pad1)") (class "Default")
      (node (ref "R19") (pin "1") (pinfunction "1_1") (pintype "passive"))
      (node (ref "R20") (pin "1") (pinfunction "1_1") (pintype "passive"))
      (node (ref "T4") (pin "B") (pinfunction "B_B") (pintype "passive"))
    )
    (net (code "56") (name "Net-(R21-Pad1)") (class "Default")
      (node (ref "R21") (pin "1") (pinfunction "1_1") (pintype "passive"))
      (node (ref "R22") (pin "1") (pinfunction "1_1") (pintype "passive"))
      (node (ref "T5") (pin "B") (pinfunction "B_B") (pintype "passive"))
    )
    (net (code "57") (name "Net-(R24-Pad1)") (class "Default")
      (node (ref "R24") (pin "1") (pinfunction "1_1") (pintype "passive"))
      (node (ref "T6") (pin "C") (pinfunction "C_C") (pintype "passive"))
    )
    (net (code "58") (name "Net-(R25-Pad1)") (class "Default")
      (node (ref "R25") (pin "1") (pinfunction "1_1") (pintype "passive"))
      (node (ref "T6") (pin "B") (pinfunction "B_B") (pintype "passive"))
    )
    (net (code "59") (name "Net-(R26-Pad1)") (class "Default")
      (node (ref "R26") (pin "1") (pinfunction "1_1") (pintype "passive"))
      (node (ref "T7") (pin "B") (pinfunction "B_B") (pintype "passive"))
    )
    (net (code "60") (name "Net-(R27-Pad2)") (class "Default")
      (node (ref "R27") (pin "2") (pinfunction "2_2") (pintype "passive"))
      (node (ref "R28") (pin "1") (pinfunction "1_1") (pintype "passive"))
    )
    (net (code "61") (name "Net-(R32-Pad1)") (class "Default")
      (node (ref "R32") (pin "1") (pinfunction "1_1") (pintype "passive"))
      (node (ref "T8") (pin "B") (pinfunction "B_B") (pintype "passive"))
    )
    (net (code "62") (name "Net-(R33-Pad1)") (class "Default")
      (node (ref "R33") (pin "1") (pinfunction "1_1") (pintype "passive"))
      (node (ref "T9") (pin "B") (pinfunction "B_B") (pintype "passive"))
    )
    (net (code "63") (name "Net-(R34-Pad1)") (class "Default")
      (node (ref "R34") (pin "1") (pinfunction "1_1") (pintype "passive"))
      (node (ref "T10") (pin "B") (pinfunction "B_B") (pintype "passive"))
    )
    (net (code "64") (name "Net-(R35-Pad1)") (class "Default")
      (node (ref "R35") (pin "1") (pinfunction "1_1") (pintype "passive"))
      (node (ref "T11") (pin "B") (pinfunction "B_B") (pintype "passive"))
    )
    (net (code "65") (name "Net-(R36-Pad1)") (class "Default")
      (node (ref "R36") (pin "1") (pinfunction "1_1") (pintype "passive"))
      (node (ref "T12") (pin "B") (pinfunction "B_B") (pintype "passive"))
    )
    (net (code "66") (name "Net-(T-B)") (class "Default")
      (node (ref "R23") (pin "1") (pinfunction "1_1") (pintype "passive"))
      (node (ref "R24") (pin "2") (pinfunction "2_2") (pintype "passive"))
      (node (ref "T") (pin "1") (pinfunction "B_1") (pintype "passive"))
    )
    (net (code "67") (name "Net-(T3-B)") (class "Default")
      (node (ref "R13") (pin "1") (pinfunction "1_1") (pintype "passive"))
      (node (ref "R14") (pin "1") (pinfunction "1_1") (pintype "passive"))
      (node (ref "T3") (pin "1") (pinfunction "B_1") (pintype "passive"))
    )
    (net (code "68") (name "Net-(T13-B)") (class "Default")
      (node (ref "R38") (pin "2") (pinfunction "2_2") (pintype "passive"))
      (node (ref "R39") (pin "2") (pinfunction "2_2") (pintype "passive"))
      (node (ref "T13") (pin "1") (pinfunction "B_1") (pintype "passive"))
      (node (ref "T13") (pin "2") (pinfunction "C_2") (pintype "passive"))
      (node (ref "T14") (pin "1") (pinfunction "B_1") (pintype "passive"))
      (node (ref "X2") (pin "1") (pinfunction "S_1") (pintype "passive"))
    )
    (net (code "69") (name "Net-(T13-E)") (class "Default")
      (node (ref "R40") (pin "1") (pinfunction "1_1") (pintype "passive"))
      (node (ref "T13") (pin "3") (pinfunction "E_3") (pintype "passive"))
    )
    (net (code "70") (name "Net-(T14-E)") (class "Default")
      (node (ref "R41") (pin "1") (pinfunction "1_1") (pintype "passive"))
      (node (ref "T14") (pin "3") (pinfunction "E_3") (pintype "passive"))
    )
    (net (code "71") (name "Net-(TACHO_BELEUCHTUNG-PP)") (class "Default")
      (node (ref "TACHO_BELEUCHTUNG") (pin "TP") (pinfunction "PP_TP") (pintype "input"))
      (node (ref "X1") (pin "24") (pinfunction "24_24") (pintype "passive"))
    )
    (net (code "72") (name "Net-(ZüNDSPULE-PP)") (class "Default")
      (node (ref "X1") (pin "16") (pinfunction "16_16") (pintype "passive"))
      (node (ref "ZüNDSPULE") (pin "TP") (pinfunction "PP_TP") (pintype "input"))
    )
    (net (code "73") (name "VCC") (class "Default")
      (node (ref "C4") (pin "1") (pinfunction "1_1") (pintype "passive"))
      (node (ref "IC1") (pin "OUT") (pinfunction "OUT_OUT") (pintype "passive"))
      (node (ref "IC2") (pin "8") (pinfunction "V+_8") (pintype "power_in"))
      (node (ref "IC5") (pin "8") (pinfunction "V+_8") (pintype "power_in"))
      (node (ref "R15") (pin "2") (pinfunction "2_2") (pintype "passive"))
      (node (ref "R6") (pin "2") (pinfunction "2_2") (pintype "passive"))
    )
    (net (code "74") (name "unconnected-(IC3A-Q6-Pad7)") (class "Default")
      (node (ref "IC3") (pin "7") (pinfunction "Q6_7") (pintype "output"))
    )
    (net (code "75") (name "unconnected-(IC3A-Q7-Pad4)") (class "Default")
      (node (ref "IC3") (pin "4") (pinfunction "Q7_4") (pintype "output"))
    )
    (net (code "76") (name "unconnected-(IC3A-Q8-Pad9)") (class "Default")
      (node (ref "IC3") (pin "9") (pinfunction "Q8_9") (pintype "output"))
    )
    (net (code "77") (name "unconnected-(IC3A-Q9-Pad5)") (class "Default")
      (node (ref "IC3") (pin "5") (pinfunction "Q9_5") (pintype "output"))
    )
    (net (code "78") (name "unconnected-(T-C{slash}-Pad4)") (class "Default")
      (node (ref "T") (pin "4") (pinfunction "C/_4") (pintype "passive"))
    )
    (net (code "79") (name "unconnected-(T3-C{slash}-Pad4)") (class "Default")
      (node (ref "T3") (pin "4") (pinfunction "C/_4") (pintype "passive"))
    )
    (net (code "80") (name "unconnected-(T13-C{slash}-Pad4)") (class "Default")
      (node (ref "T13") (pin "4") (pinfunction "C/_4") (pintype "passive"))
    )
    (net (code "81") (name "unconnected-(T14-C{slash}-Pad4)") (class "Default")
      (node (ref "T14") (pin "4") (pinfunction "C/_4") (pintype "passive"))
    )
    (net (code "82") (name "unconnected-(X1-Pad20)") (class "Default")
      (node (ref "X1") (pin "20") (pinfunction "20_20") (pintype "passive"))
    )
  )
)
